# Debug_Board.net
KiCad netlist of a schematic drawn in EAGLE
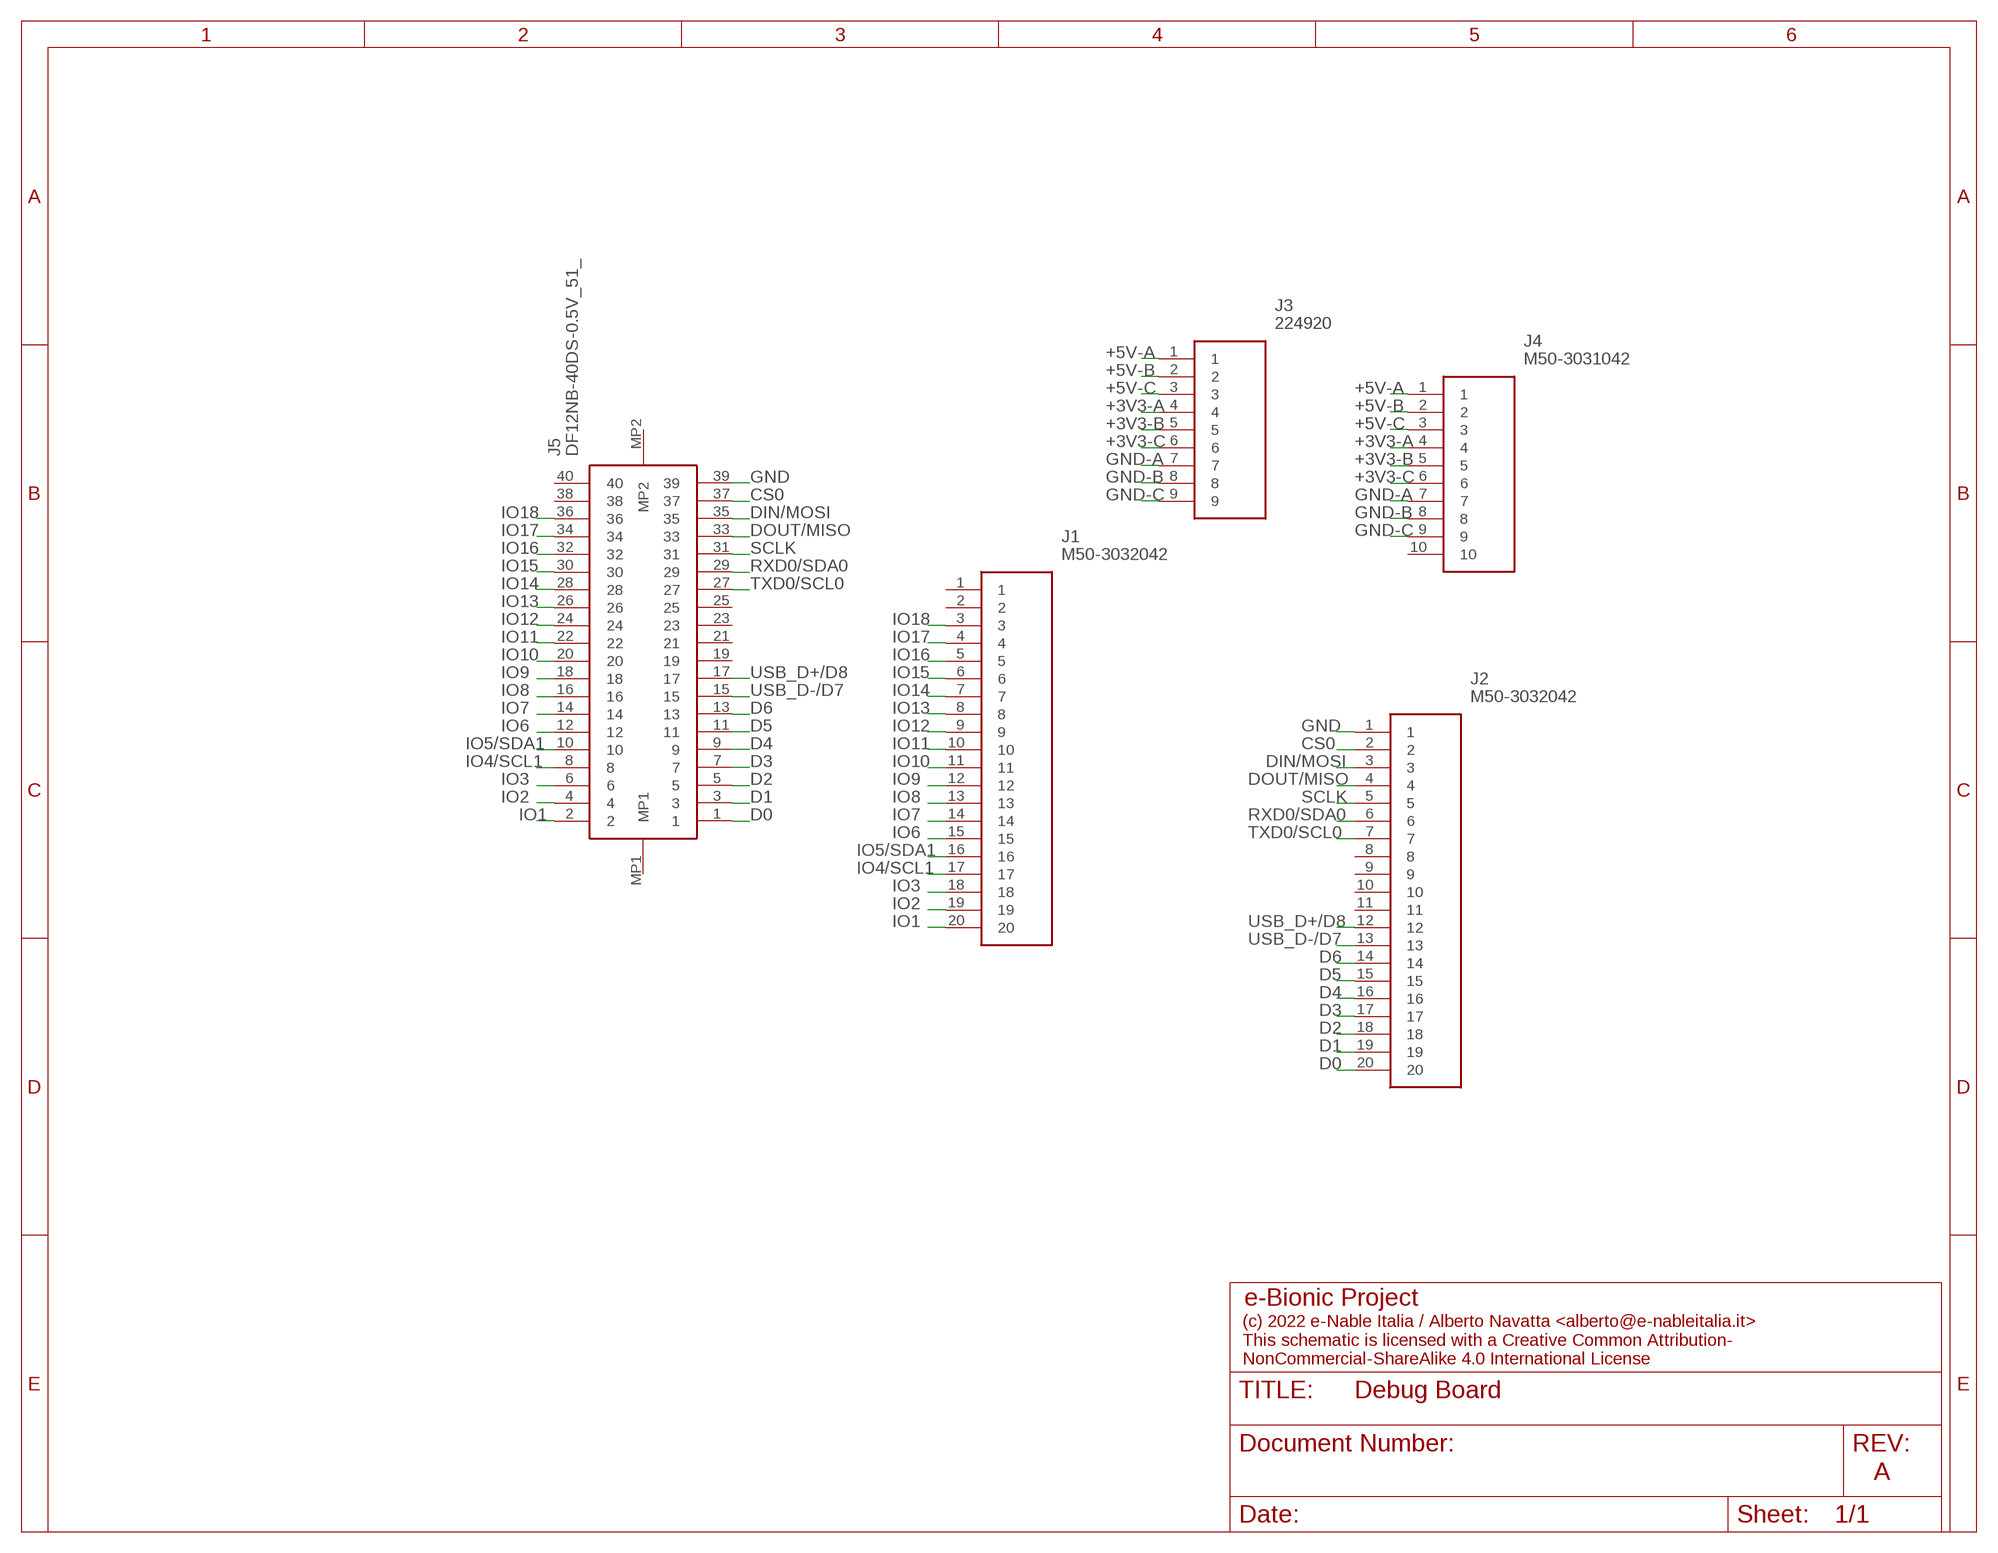
[diagram p0: schematic, sheet 1]

(export (version "E")
  (design (tool "Eeschema 10.0.6"))
  (components
    (comp (ref "J1")
      (value "M50-3032042")
      (footprint "eagle-import:M503032042")
      (fields (field (name "MOUSER_PART_NUMBER") "855-M50-3032042"))
      (libsource (lib "eagle-import") (part "M50-3032042"))
    )
    (comp (ref "J2")
      (value "M50-3032042")
      (footprint "eagle-import:M503032042")
      (fields (field (name "MOUSER_PART_NUMBER") "855-M50-3032042"))
      (libsource (lib "eagle-import") (part "M50-3032042"))
    )
    (comp (ref "J3")
      (value "224920")
      (footprint "eagle-import:224920")
      (fields (field (name "MOUSER_PART_NUMBER") "305-224920"))
      (libsource (lib "eagle-import") (part "224920"))
    )
    (comp (ref "J4")
      (value "M50-3031042")
      (footprint "eagle-import:M503031042")
      (fields (field (name "MOUSER_PART_NUMBER") "855-M50-3031042"))
      (libsource (lib "eagle-import") (part "M50-3031042"))
    )
    (comp (ref "J5")
      (value "DF12NB-40DS-0.5V_51_")
      (footprint "eagle-import:DF12NB40DS05V51")
      (fields
        (field (name "MANUFACTURER_PART_NUMBER") "DF12NB-40DS-0.5V(51)")
        (field (name "MOUSER_PART_NUMBER") "798-DF12NB40DS0551")
      )
      (libsource (lib "eagle-import") (part "DF12NB-40DS-0.5V_51_"))
    )
  )
  (nets
    (net (code "1") (name "/+3V3-A") (class "Default")
      (node (ref "J3") (pin "4") (pinfunction "4_4") (pintype "bidirectional"))
      (node (ref "J4") (pin "4") (pinfunction "4_4") (pintype "bidirectional"))
    )
    (net (code "2") (name "/+3V3-B") (class "Default")
      (node (ref "J3") (pin "5") (pinfunction "5_5") (pintype "bidirectional"))
      (node (ref "J4") (pin "5") (pinfunction "5_5") (pintype "bidirectional"))
    )
    (net (code "3") (name "/+3V3-C") (class "Default")
      (node (ref "J3") (pin "6") (pinfunction "6_6") (pintype "bidirectional"))
      (node (ref "J4") (pin "6") (pinfunction "6_6") (pintype "bidirectional"))
    )
    (net (code "4") (name "/+5V-A") (class "Default")
      (node (ref "J3") (pin "1") (pinfunction "1_1") (pintype "bidirectional"))
      (node (ref "J4") (pin "1") (pinfunction "1_1") (pintype "bidirectional"))
    )
    (net (code "5") (name "/+5V-B") (class "Default")
      (node (ref "J3") (pin "2") (pinfunction "2_2") (pintype "bidirectional"))
      (node (ref "J4") (pin "2") (pinfunction "2_2") (pintype "bidirectional"))
    )
    (net (code "6") (name "/+5V-C") (class "Default")
      (node (ref "J3") (pin "3") (pinfunction "3_3") (pintype "bidirectional"))
      (node (ref "J4") (pin "3") (pinfunction "3_3") (pintype "bidirectional"))
    )
    (net (code "7") (name "/CS0") (class "Default")
      (node (ref "J2") (pin "2") (pinfunction "2_2") (pintype "bidirectional"))
      (node (ref "J5") (pin "37") (pinfunction "37_37") (pintype "bidirectional"))
    )
    (net (code "8") (name "/D0") (class "Default")
      (node (ref "J2") (pin "20") (pinfunction "20_20") (pintype "bidirectional"))
      (node (ref "J5") (pin "1") (pinfunction "1_1") (pintype "bidirectional"))
    )
    (net (code "9") (name "/D1") (class "Default")
      (node (ref "J2") (pin "19") (pinfunction "19_19") (pintype "bidirectional"))
      (node (ref "J5") (pin "3") (pinfunction "3_3") (pintype "bidirectional"))
    )
    (net (code "10") (name "/D2") (class "Default")
      (node (ref "J2") (pin "18") (pinfunction "18_18") (pintype "bidirectional"))
      (node (ref "J5") (pin "5") (pinfunction "5_5") (pintype "bidirectional"))
    )
    (net (code "11") (name "/D3") (class "Default")
      (node (ref "J2") (pin "17") (pinfunction "17_17") (pintype "bidirectional"))
      (node (ref "J5") (pin "7") (pinfunction "7_7") (pintype "bidirectional"))
    )
    (net (code "12") (name "/D4") (class "Default")
      (node (ref "J2") (pin "16") (pinfunction "16_16") (pintype "bidirectional"))
      (node (ref "J5") (pin "9") (pinfunction "9_9") (pintype "bidirectional"))
    )
    (net (code "13") (name "/D5") (class "Default")
      (node (ref "J2") (pin "15") (pinfunction "15_15") (pintype "bidirectional"))
      (node (ref "J5") (pin "11") (pinfunction "11_11") (pintype "bidirectional"))
    )
    (net (code "14") (name "/D6") (class "Default")
      (node (ref "J2") (pin "14") (pinfunction "14_14") (pintype "bidirectional"))
      (node (ref "J5") (pin "13") (pinfunction "13_13") (pintype "bidirectional"))
    )
    (net (code "15") (name "/DIN{slash}MOSI") (class "Default")
      (node (ref "J2") (pin "3") (pinfunction "3_3") (pintype "bidirectional"))
      (node (ref "J5") (pin "35") (pinfunction "35_35") (pintype "bidirectional"))
    )
    (net (code "16") (name "/DOUT{slash}MISO") (class "Default")
      (node (ref "J2") (pin "4") (pinfunction "4_4") (pintype "bidirectional"))
      (node (ref "J5") (pin "33") (pinfunction "33_33") (pintype "bidirectional"))
    )
    (net (code "17") (name "/GND") (class "Default")
      (node (ref "J2") (pin "1") (pinfunction "1_1") (pintype "bidirectional"))
      (node (ref "J5") (pin "39") (pinfunction "39_39") (pintype "bidirectional"))
    )
    (net (code "18") (name "/GND-A") (class "Default")
      (node (ref "J3") (pin "7") (pinfunction "7_7") (pintype "bidirectional"))
      (node (ref "J4") (pin "7") (pinfunction "7_7") (pintype "bidirectional"))
    )
    (net (code "19") (name "/GND-B") (class "Default")
      (node (ref "J3") (pin "8") (pinfunction "8_8") (pintype "bidirectional"))
      (node (ref "J4") (pin "8") (pinfunction "8_8") (pintype "bidirectional"))
    )
    (net (code "20") (name "/GND-C") (class "Default")
      (node (ref "J3") (pin "9") (pinfunction "9_9") (pintype "bidirectional"))
      (node (ref "J4") (pin "9") (pinfunction "9_9") (pintype "bidirectional"))
    )
    (net (code "21") (name "/IO1") (class "Default")
      (node (ref "J1") (pin "20") (pinfunction "20_20") (pintype "bidirectional"))
      (node (ref "J5") (pin "2") (pinfunction "2_2") (pintype "bidirectional"))
    )
    (net (code "22") (name "/IO2") (class "Default")
      (node (ref "J1") (pin "19") (pinfunction "19_19") (pintype "bidirectional"))
      (node (ref "J5") (pin "4") (pinfunction "4_4") (pintype "bidirectional"))
    )
    (net (code "23") (name "/IO3") (class "Default")
      (node (ref "J1") (pin "18") (pinfunction "18_18") (pintype "bidirectional"))
      (node (ref "J5") (pin "6") (pinfunction "6_6") (pintype "bidirectional"))
    )
    (net (code "24") (name "/IO4{slash}SCL1") (class "Default")
      (node (ref "J1") (pin "17") (pinfunction "17_17") (pintype "bidirectional"))
      (node (ref "J5") (pin "8") (pinfunction "8_8") (pintype "bidirectional"))
    )
    (net (code "25") (name "/IO5{slash}SDA1") (class "Default")
      (node (ref "J1") (pin "16") (pinfunction "16_16") (pintype "bidirectional"))
      (node (ref "J5") (pin "10") (pinfunction "10_10") (pintype "bidirectional"))
    )
    (net (code "26") (name "/IO6") (class "Default")
      (node (ref "J1") (pin "15") (pinfunction "15_15") (pintype "bidirectional"))
      (node (ref "J5") (pin "12") (pinfunction "12_12") (pintype "bidirectional"))
    )
    (net (code "27") (name "/IO7") (class "Default")
      (node (ref "J1") (pin "14") (pinfunction "14_14") (pintype "bidirectional"))
      (node (ref "J5") (pin "14") (pinfunction "14_14") (pintype "bidirectional"))
    )
    (net (code "28") (name "/IO8") (class "Default")
      (node (ref "J1") (pin "13") (pinfunction "13_13") (pintype "bidirectional"))
      (node (ref "J5") (pin "16") (pinfunction "16_16") (pintype "bidirectional"))
    )
    (net (code "29") (name "/IO9") (class "Default")
      (node (ref "J1") (pin "12") (pinfunction "12_12") (pintype "bidirectional"))
      (node (ref "J5") (pin "18") (pinfunction "18_18") (pintype "bidirectional"))
    )
    (net (code "30") (name "/IO10") (class "Default")
      (node (ref "J1") (pin "11") (pinfunction "11_11") (pintype "bidirectional"))
      (node (ref "J5") (pin "20") (pinfunction "20_20") (pintype "bidirectional"))
    )
    (net (code "31") (name "/IO11") (class "Default")
      (node (ref "J1") (pin "10") (pinfunction "10_10") (pintype "bidirectional"))
      (node (ref "J5") (pin "22") (pinfunction "22_22") (pintype "bidirectional"))
    )
    (net (code "32") (name "/IO12") (class "Default")
      (node (ref "J1") (pin "9") (pinfunction "9_9") (pintype "bidirectional"))
      (node (ref "J5") (pin "24") (pinfunction "24_24") (pintype "bidirectional"))
    )
    (net (code "33") (name "/IO13") (class "Default")
      (node (ref "J1") (pin "8") (pinfunction "8_8") (pintype "bidirectional"))
      (node (ref "J5") (pin "26") (pinfunction "26_26") (pintype "bidirectional"))
    )
    (net (code "34") (name "/IO14") (class "Default")
      (node (ref "J1") (pin "7") (pinfunction "7_7") (pintype "bidirectional"))
      (node (ref "J5") (pin "28") (pinfunction "28_28") (pintype "bidirectional"))
    )
    (net (code "35") (name "/IO15") (class "Default")
      (node (ref "J1") (pin "6") (pinfunction "6_6") (pintype "bidirectional"))
      (node (ref "J5") (pin "30") (pinfunction "30_30") (pintype "bidirectional"))
    )
    (net (code "36") (name "/IO16") (class "Default")
      (node (ref "J1") (pin "5") (pinfunction "5_5") (pintype "bidirectional"))
      (node (ref "J5") (pin "32") (pinfunction "32_32") (pintype "bidirectional"))
    )
    (net (code "37") (name "/IO17") (class "Default")
      (node (ref "J1") (pin "4") (pinfunction "4_4") (pintype "bidirectional"))
      (node (ref "J5") (pin "34") (pinfunction "34_34") (pintype "bidirectional"))
    )
    (net (code "38") (name "/IO18") (class "Default")
      (node (ref "J1") (pin "3") (pinfunction "3_3") (pintype "bidirectional"))
      (node (ref "J5") (pin "36") (pinfunction "36_36") (pintype "bidirectional"))
    )
    (net (code "39") (name "/RXD0{slash}SDA0") (class "Default")
      (node (ref "J2") (pin "6") (pinfunction "6_6") (pintype "bidirectional"))
      (node (ref "J5") (pin "29") (pinfunction "29_29") (pintype "bidirectional"))
    )
    (net (code "40") (name "/SCLK") (class "Default")
      (node (ref "J2") (pin "5") (pinfunction "5_5") (pintype "bidirectional"))
      (node (ref "J5") (pin "31") (pinfunction "31_31") (pintype "bidirectional"))
    )
    (net (code "41") (name "/TXD0{slash}SCL0") (class "Default")
      (node (ref "J2") (pin "7") (pinfunction "7_7") (pintype "bidirectional"))
      (node (ref "J5") (pin "27") (pinfunction "27_27") (pintype "bidirectional"))
    )
    (net (code "42") (name "/USB_D+{slash}D8") (class "Default")
      (node (ref "J2") (pin "12") (pinfunction "12_12") (pintype "bidirectional"))
      (node (ref "J5") (pin "17") (pinfunction "17_17") (pintype "bidirectional"))
    )
    (net (code "43") (name "/USB_D-{slash}D7") (class "Default")
      (node (ref "J2") (pin "13") (pinfunction "13_13") (pintype "bidirectional"))
      (node (ref "J5") (pin "15") (pinfunction "15_15") (pintype "bidirectional"))
    )
    (net (code "44") (name "unconnected-(J1-Pad1)") (class "Default")
      (node (ref "J1") (pin "1") (pinfunction "1_1") (pintype "bidirectional"))
    )
    (net (code "45") (name "unconnected-(J1-Pad2)") (class "Default")
      (node (ref "J1") (pin "2") (pinfunction "2_2") (pintype "bidirectional"))
    )
    (net (code "46") (name "unconnected-(J2-Pad8)") (class "Default")
      (node (ref "J2") (pin "8") (pinfunction "8_8") (pintype "bidirectional"))
    )
    (net (code "47") (name "unconnected-(J2-Pad9)") (class "Default")
      (node (ref "J2") (pin "9") (pinfunction "9_9") (pintype "bidirectional"))
    )
    (net (code "48") (name "unconnected-(J2-Pad10)") (class "Default")
      (node (ref "J2") (pin "10") (pinfunction "10_10") (pintype "bidirectional"))
    )
    (net (code "49") (name "unconnected-(J2-Pad11)") (class "Default")
      (node (ref "J2") (pin "11") (pinfunction "11_11") (pintype "bidirectional"))
    )
    (net (code "50") (name "unconnected-(J4-Pad10)") (class "Default")
      (node (ref "J4") (pin "10") (pinfunction "10_10") (pintype "bidirectional"))
    )
    (net (code "51") (name "unconnected-(J5-Pad19)") (class "Default")
      (node (ref "J5") (pin "19") (pinfunction "19_19") (pintype "bidirectional"))
    )
    (net (code "52") (name "unconnected-(J5-Pad21)") (class "Default")
      (node (ref "J5") (pin "21") (pinfunction "21_21") (pintype "bidirectional"))
    )
    (net (code "53") (name "unconnected-(J5-Pad23)") (class "Default")
      (node (ref "J5") (pin "23") (pinfunction "23_23") (pintype "bidirectional"))
    )
    (net (code "54") (name "unconnected-(J5-Pad25)") (class "Default")
      (node (ref "J5") (pin "25") (pinfunction "25_25") (pintype "bidirectional"))
    )
    (net (code "55") (name "unconnected-(J5-Pad38)") (class "Default")
      (node (ref "J5") (pin "38") (pinfunction "38_38") (pintype "bidirectional"))
    )
    (net (code "56") (name "unconnected-(J5-Pad40)") (class "Default")
      (node (ref "J5") (pin "40") (pinfunction "40_40") (pintype "bidirectional"))
    )
    (net (code "57") (name "unconnected-(J5-PadMP1)") (class "Default")
      (node (ref "J5") (pin "MP1") (pinfunction "MP1_MP1") (pintype "bidirectional"))
    )
    (net (code "58") (name "unconnected-(J5-PadMP2)") (class "Default")
      (node (ref "J5") (pin "MP2") (pinfunction "MP2_MP2") (pintype "bidirectional"))
    )
  )
)
